# 3_ESP8266_Core.net
KiCad netlist of a schematic drawn in Altium Designer
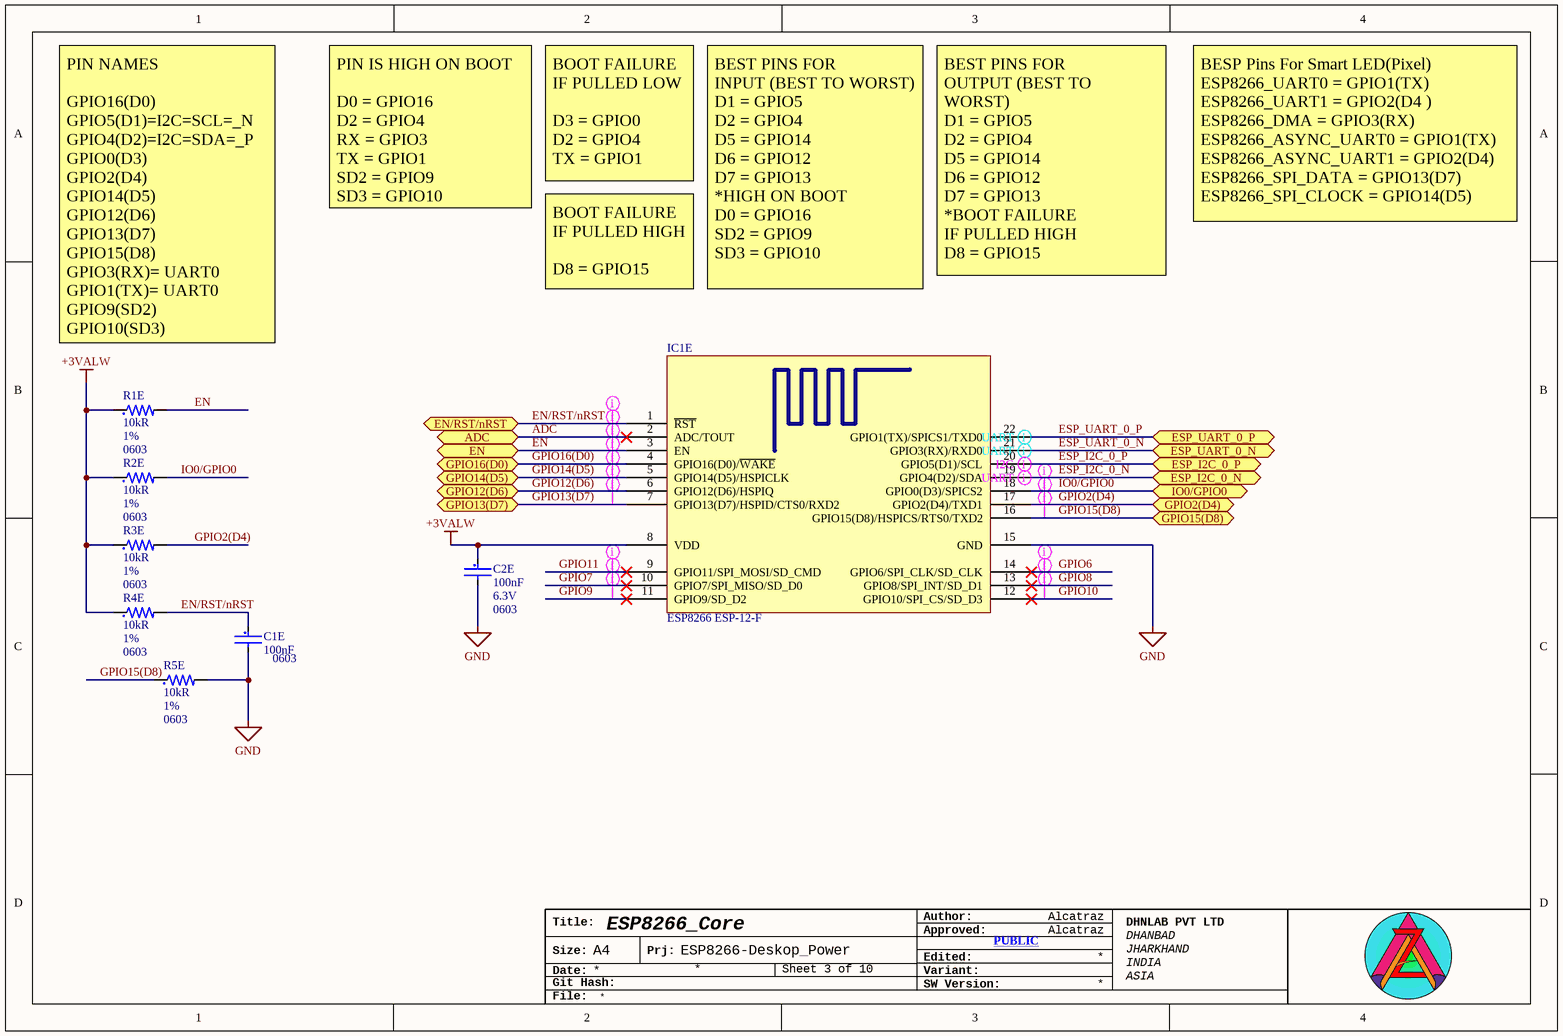
[diagram p0: 3_ESP8266_Core.SchDoc]

(export (version "E")
  (design (tool "Eeschema 10.0.6"))
  (components
    (comp (ref "C1E")
      (value "100nF")
      (footprint "C0603-IPC_C_No_Silk")
      (description "Cap Cer 0.1UF 6.3V X7R 0603")
      (fields
        (field (name "MANUFACTURER") "KYOCERA AVX")
        (field (name "MANUFACTURER PART NUMBER") "KGM15AR70J104KM")
        (field (name "PACKAGE") "0603")
      )
      (libsource (lib "Lib_Capacitor_0603") (part "100nF_6.3V"))
    )
    (comp (ref "C2E")
      (value "100nF")
      (footprint "C0603-IPC_C_No_Silk")
      (description "Cap Cer 0.1UF 6.3V X7R 0603")
      (fields
        (field (name "MANUFACTURER") "KYOCERA AVX")
        (field (name "MANUFACTURER PART NUMBER") "KGM15AR70J104KM")
        (field (name "VOLTAGE") "6.3V")
        (field (name "PACKAGE") "0603")
      )
      (libsource (lib "Lib_Capacitor_0603") (part "100nF_6.3V"))
    )
    (comp (ref "IC1E")
      (value "ESP8266 ESP-12-F")
      (footprint "ESP8266 ESP-12-Large")
      (libsource (lib "Lib_ESP8266") (part "ESP8266 ESP-12-F"))
    )
    (comp (ref "R1E")
      (value "10kR")
      (footprint "R0603-MFG")
      (description "SMD Chip Resistor, 10 kOhm, ± 1%, 100 mW, 0603 [1608 Metric], Thick Film, General Purpose")
      (fields
        (field (name "MANUFACTURER") "Yageo")
        (field (name "MANUFACTURER PART NUMBER") "RC0603FR-0710KL")
        (field (name "TOLERANCE") "1%")
        (field (name "CASE/PACKAGE") "0603")
      )
      (libsource (lib "Lib_Register_0603") (part "10K"))
    )
    (comp (ref "R2E")
      (value "10kR")
      (footprint "R0603-MFG")
      (description "SMD Chip Resistor, 10 kOhm, ± 1%, 100 mW, 0603 [1608 Metric], Thick Film, General Purpose")
      (fields
        (field (name "MANUFACTURER") "Yageo")
        (field (name "MANUFACTURER PART NUMBER") "RC0603FR-0710KL")
        (field (name "TOLERANCE") "1%")
        (field (name "CASE/PACKAGE") "0603")
      )
      (libsource (lib "Lib_Register_0603") (part "10K"))
    )
    (comp (ref "R3E")
      (value "10kR")
      (footprint "R0603-MFG")
      (description "SMD Chip Resistor, 10 kOhm, ± 1%, 100 mW, 0603 [1608 Metric], Thick Film, General Purpose")
      (fields
        (field (name "MANUFACTURER") "Yageo")
        (field (name "MANUFACTURER PART NUMBER") "RC0603FR-0710KL")
        (field (name "TOLERANCE") "1%")
        (field (name "CASE/PACKAGE") "0603")
      )
      (libsource (lib "Lib_Register_0603") (part "10K"))
    )
    (comp (ref "R4E")
      (value "10kR")
      (footprint "R0603-MFG")
      (description "SMD Chip Resistor, 10 kOhm, ± 1%, 100 mW, 0603 [1608 Metric], Thick Film, General Purpose")
      (fields
        (field (name "MANUFACTURER") "Yageo")
        (field (name "MANUFACTURER PART NUMBER") "RC0603FR-0710KL")
        (field (name "TOLERANCE") "1%")
        (field (name "CASE/PACKAGE") "0603")
      )
      (libsource (lib "Lib_Register_0603") (part "10K"))
    )
    (comp (ref "R5E")
      (value "10kR")
      (footprint "R0603-MFG")
      (description "SMD Chip Resistor, 10 kOhm, ± 1%, 100 mW, 0603 [1608 Metric], Thick Film, General Purpose")
      (fields
        (field (name "MANUFACTURER") "Yageo")
        (field (name "MANUFACTURER PART NUMBER") "RC0603FR-0710KL")
        (field (name "TOLERANCE") "1%")
        (field (name "CASE/PACKAGE") "0603")
      )
      (libsource (lib "Lib_Register_0603") (part "10K"))
    )
  )
  (nets
    (net (code "1") (name "+3VALW") (class "Default")
      (node (ref "C2E") (pin "1") (pinfunction "1_1") (pintype "passive"))
      (node (ref "IC1E") (pin "8") (pinfunction "VDD_8") (pintype "passive"))
      (node (ref "R1E") (pin "1") (pinfunction "1_1") (pintype "passive"))
      (node (ref "R2E") (pin "1") (pinfunction "1_1") (pintype "passive"))
      (node (ref "R3E") (pin "1") (pinfunction "1_1") (pintype "passive"))
      (node (ref "R4E") (pin "1") (pinfunction "1_1") (pintype "passive"))
    )
    (net (code "2") (name "/ADC") (class "Default")
      (node (ref "IC1E") (pin "2") (pinfunction "ADC/TOUT_2") (pintype "passive+no_connect"))
    )
    (net (code "3") (name "/EN") (class "Default")
      (node (ref "IC1E") (pin "3") (pinfunction "EN_3") (pintype "passive"))
      (node (ref "R1E") (pin "2") (pinfunction "2_2") (pintype "passive"))
    )
    (net (code "4") (name "/EN{slash}RST{slash}nRST") (class "Default")
      (node (ref "C1E") (pin "1") (pinfunction "1_1") (pintype "passive"))
      (node (ref "IC1E") (pin "1") (pinfunction "~{RST}_1") (pintype "passive"))
      (node (ref "R4E") (pin "2") (pinfunction "2_2") (pintype "passive"))
    )
    (net (code "5") (name "/ESP_I2C_0_N") (class "Default")
      (node (ref "IC1E") (pin "19") (pinfunction "GPIO4(D2)/SDA_19") (pintype "passive"))
    )
    (net (code "6") (name "/ESP_I2C_0_P") (class "Default")
      (node (ref "IC1E") (pin "20") (pinfunction "GPIO5(D1)/SCL_20") (pintype "passive"))
    )
    (net (code "7") (name "/ESP_UART_0_N") (class "Default")
      (node (ref "IC1E") (pin "21") (pinfunction "GPIO3(RX)/RXD0_21") (pintype "passive"))
    )
    (net (code "8") (name "/ESP_UART_0_P") (class "Default")
      (node (ref "IC1E") (pin "22") (pinfunction "GPIO1(TX)/SPICS1/TXD0_22") (pintype "passive"))
    )
    (net (code "9") (name "/GPIO2(D4)") (class "Default")
      (node (ref "IC1E") (pin "17") (pinfunction "GPIO2(D4)/TXD1_17") (pintype "passive"))
      (node (ref "R3E") (pin "2") (pinfunction "2_2") (pintype "passive"))
    )
    (net (code "10") (name "/GPIO6") (class "Default")
      (node (ref "IC1E") (pin "14") (pinfunction "GPIO6/SPI_CLK/SD_CLK_14") (pintype "passive+no_connect"))
    )
    (net (code "11") (name "/GPIO7") (class "Default")
      (node (ref "IC1E") (pin "10") (pinfunction "GPIO7/SPI_MISO/SD_D0_10") (pintype "passive+no_connect"))
    )
    (net (code "12") (name "/GPIO8") (class "Default")
      (node (ref "IC1E") (pin "13") (pinfunction "GPIO8/SPI_INT/SD_D1_13") (pintype "passive+no_connect"))
    )
    (net (code "13") (name "/GPIO9") (class "Default")
      (node (ref "IC1E") (pin "11") (pinfunction "GPIO9/SD_D2_11") (pintype "passive+no_connect"))
    )
    (net (code "14") (name "/GPIO10") (class "Default")
      (node (ref "IC1E") (pin "12") (pinfunction "GPIO10/SPI_CS/SD_D3_12") (pintype "passive+no_connect"))
    )
    (net (code "15") (name "/GPIO11") (class "Default")
      (node (ref "IC1E") (pin "9") (pinfunction "GPIO11/SPI_MOSI/SD_CMD_9") (pintype "passive+no_connect"))
    )
    (net (code "16") (name "/GPIO12(D6)") (class "Default")
      (node (ref "IC1E") (pin "6") (pinfunction "GPIO12(D6)/HSPIQ_6") (pintype "passive"))
    )
    (net (code "17") (name "/GPIO13(D7)") (class "Default")
      (node (ref "IC1E") (pin "7") (pinfunction "GPIO13(D7)/HSPID/CTS0/RXD2_7") (pintype "passive"))
    )
    (net (code "18") (name "/GPIO14(D5)") (class "Default")
      (node (ref "IC1E") (pin "5") (pinfunction "GPIO14(D5)/HSPICLK_5") (pintype "passive"))
    )
    (net (code "19") (name "/GPIO15(D8)") (class "Default")
      (node (ref "IC1E") (pin "16") (pinfunction "GPIO15(D8)/HSPICS/RTS0/TXD2_16") (pintype "passive"))
      (node (ref "R5E") (pin "1") (pinfunction "1_1") (pintype "passive"))
    )
    (net (code "20") (name "/GPIO16(D0)") (class "Default")
      (node (ref "IC1E") (pin "4") (pinfunction "GPIO16(D0)/~{WAKE}_4") (pintype "passive"))
    )
    (net (code "21") (name "/IO0{slash}GPIO0") (class "Default")
      (node (ref "IC1E") (pin "18") (pinfunction "GPIO0(D3)/SPICS2_18") (pintype "passive"))
      (node (ref "R2E") (pin "2") (pinfunction "2_2") (pintype "passive"))
    )
    (net (code "22") (name "GND") (class "Default")
      (node (ref "C1E") (pin "2") (pinfunction "2_2") (pintype "passive"))
      (node (ref "C2E") (pin "2") (pinfunction "2_2") (pintype "passive"))
      (node (ref "IC1E") (pin "15") (pinfunction "GND_15") (pintype "passive"))
      (node (ref "R5E") (pin "2") (pinfunction "2_2") (pintype "passive"))
    )
  )
)
